# CMP.net
KiCad netlist of a schematic drawn in Altium Designer
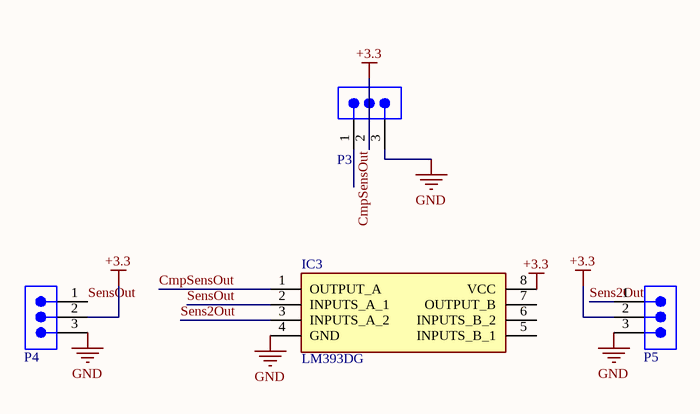
[diagram p0: CMP.SchDoc]

(export (version "E")
  (design (tool "Eeschema 10.0.6"))
  (components
    (comp (ref "IC3")
      (value "LM393DG")
      (footprint "SOIC127P600X175-8N")
      (description "Integrated Circuit")
      (fields (field (name "MOUSER PART NUMBER") "863-LM393DG"))
      (libsource (lib "CSMS") (part "LM393DG"))
    )
    (comp (ref "P3")
      (value "61300311021")
      (footprint "61300311021")
      (description "WR-PHD Pin Header, THT, Angled, pitch 2.54mm, 1 Row, 3P")
      (fields (field (name "MANUFACTURER") "Wurth Elektronik"))
      (libsource (lib "CSMS") (part "61300311021"))
    )
    (comp (ref "P4")
      (value "61300311021")
      (footprint "61300311021")
      (description "WR-PHD Pin Header, THT, Angled, pitch 2.54mm, 1 Row, 3P")
      (fields (field (name "MANUFACTURER") "Wurth Elektronik"))
      (libsource (lib "CSMS") (part "61300311021"))
    )
    (comp (ref "P5")
      (value "61300311021")
      (footprint "61300311021")
      (description "WR-PHD Pin Header, THT, Angled, pitch 2.54mm, 1 Row, 3P")
      (fields (field (name "MANUFACTURER") "Wurth Elektronik"))
      (libsource (lib "CSMS") (part "61300311021"))
    )
  )
  (nets
    (net (code "1") (name "+3.3") (class "Default")
      (node (ref "IC3") (pin "8") (pinfunction "VCC_8") (pintype "passive"))
      (node (ref "P3") (pin "2") (pinfunction "2_2") (pintype "passive"))
      (node (ref "P4") (pin "2") (pinfunction "2_2") (pintype "passive"))
      (node (ref "P5") (pin "2") (pinfunction "2_2") (pintype "passive"))
    )
    (net (code "2") (name "/CmpSensOut") (class "Default")
      (node (ref "IC3") (pin "1") (pinfunction "OUTPUT_A_1") (pintype "passive"))
      (node (ref "P3") (pin "1") (pinfunction "1_1") (pintype "passive"))
    )
    (net (code "3") (name "/Sens2Out") (class "Default")
      (node (ref "IC3") (pin "3") (pinfunction "INPUTS_A_2_3") (pintype "passive"))
      (node (ref "P5") (pin "1") (pinfunction "1_1") (pintype "passive"))
    )
    (net (code "4") (name "/SensOut") (class "Default")
      (node (ref "IC3") (pin "2") (pinfunction "INPUTS_A_1_2") (pintype "passive"))
      (node (ref "P4") (pin "1") (pinfunction "1_1") (pintype "passive"))
    )
    (net (code "5") (name "GND") (class "Default")
      (node (ref "IC3") (pin "4") (pinfunction "GND_4") (pintype "passive"))
      (node (ref "P3") (pin "3") (pinfunction "3_3") (pintype "passive"))
      (node (ref "P4") (pin "3") (pinfunction "3_3") (pintype "passive"))
      (node (ref "P5") (pin "3") (pinfunction "3_3") (pintype "passive"))
    )
    (net (code "6") (name "unconnected-(IC3-INPUTS_B_1-Pad5)") (class "Default")
      (node (ref "IC3") (pin "5") (pinfunction "INPUTS_B_1_5") (pintype "passive"))
    )
    (net (code "7") (name "unconnected-(IC3-INPUTS_B_2-Pad6)") (class "Default")
      (node (ref "IC3") (pin "6") (pinfunction "INPUTS_B_2_6") (pintype "passive"))
    )
    (net (code "8") (name "unconnected-(IC3-OUTPUT_B-Pad7)") (class "Default")
      (node (ref "IC3") (pin "7") (pinfunction "OUTPUT_B_7") (pintype "passive"))
    )
  )
)
